# SCH_Breadboard_2022-07-15.net
KiCad netlist of a schematic drawn in EasyEDA
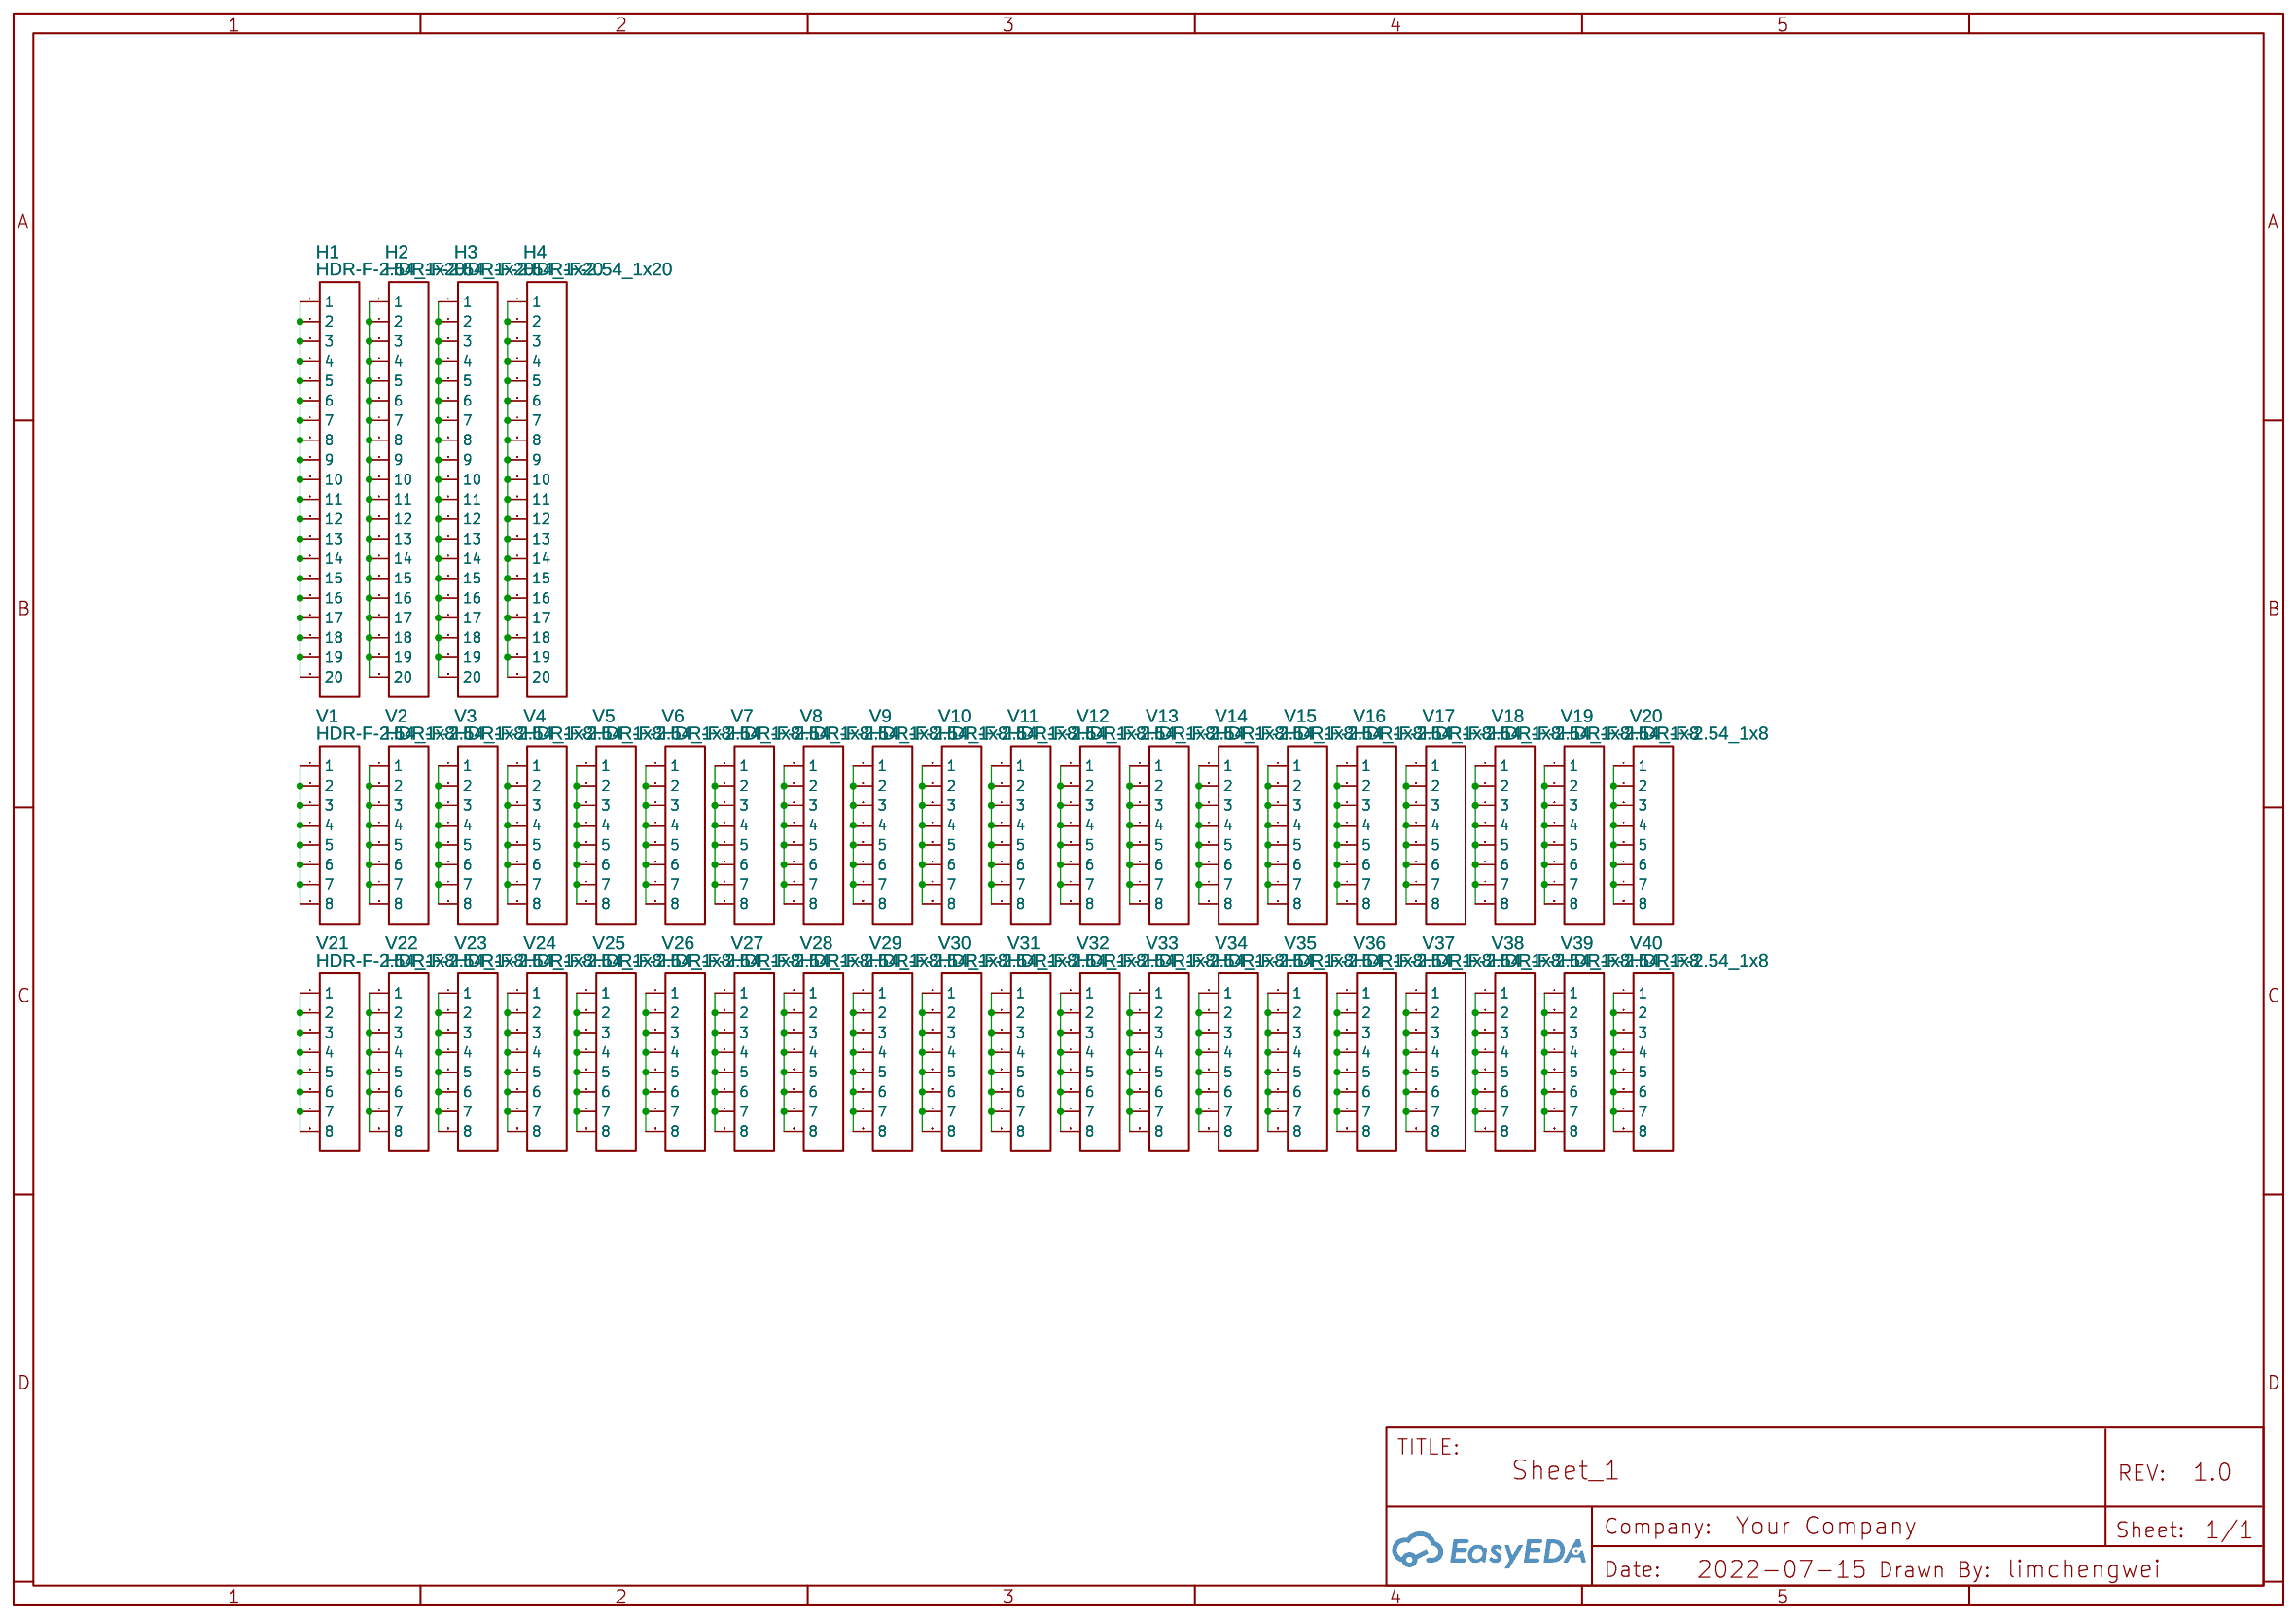
[diagram p0: schematic sheet]

(export (version "E")
  (design (tool "Eeschema 10.0.6"))
  (components
    (comp (ref "H1")
      (value "HDR-F-2.54_1x20")
      (fields (field (name "BOM_Supplier Part") "C50984"))
      (libsource (lib "") (part "HDR-F-2.54_1x20"))
    )
    (comp (ref "H2")
      (value "HDR-F-2.54_1x20")
      (fields (field (name "BOM_Supplier Part") "C50984"))
      (libsource (lib "") (part "HDR-F-2.54_1x20"))
    )
    (comp (ref "H3")
      (value "HDR-F-2.54_1x20")
      (fields (field (name "BOM_Supplier Part") "C50984"))
      (libsource (lib "") (part "HDR-F-2.54_1x20"))
    )
    (comp (ref "H4")
      (value "HDR-F-2.54_1x20")
      (fields (field (name "BOM_Supplier Part") "C50984"))
      (libsource (lib "") (part "HDR-F-2.54_1x20"))
    )
    (comp (ref "V1")
      (value "HDR-F-2.54_1x8")
      (fields (field (name "BOM_Supplier Part") "C225505"))
      (libsource (lib "") (part "HDR-F-2.54_1x8"))
    )
    (comp (ref "V2")
      (value "HDR-F-2.54_1x8")
      (fields (field (name "BOM_Supplier Part") "C225505"))
      (libsource (lib "") (part "HDR-F-2.54_1x8"))
    )
    (comp (ref "V3")
      (value "HDR-F-2.54_1x8")
      (fields (field (name "BOM_Supplier Part") "C225505"))
      (libsource (lib "") (part "HDR-F-2.54_1x8"))
    )
    (comp (ref "V4")
      (value "HDR-F-2.54_1x8")
      (fields (field (name "BOM_Supplier Part") "C225505"))
      (libsource (lib "") (part "HDR-F-2.54_1x8"))
    )
    (comp (ref "V5")
      (value "HDR-F-2.54_1x8")
      (fields (field (name "BOM_Supplier Part") "C225505"))
      (libsource (lib "") (part "HDR-F-2.54_1x8"))
    )
    (comp (ref "V6")
      (value "HDR-F-2.54_1x8")
      (fields (field (name "BOM_Supplier Part") "C225505"))
      (libsource (lib "") (part "HDR-F-2.54_1x8"))
    )
    (comp (ref "V7")
      (value "HDR-F-2.54_1x8")
      (fields (field (name "BOM_Supplier Part") "C225505"))
      (libsource (lib "") (part "HDR-F-2.54_1x8"))
    )
    (comp (ref "V8")
      (value "HDR-F-2.54_1x8")
      (fields (field (name "BOM_Supplier Part") "C225505"))
      (libsource (lib "") (part "HDR-F-2.54_1x8"))
    )
    (comp (ref "V9")
      (value "HDR-F-2.54_1x8")
      (fields (field (name "BOM_Supplier Part") "C225505"))
      (libsource (lib "") (part "HDR-F-2.54_1x8"))
    )
    (comp (ref "V10")
      (value "HDR-F-2.54_1x8")
      (fields (field (name "BOM_Supplier Part") "C225505"))
      (libsource (lib "") (part "HDR-F-2.54_1x8"))
    )
    (comp (ref "V11")
      (value "HDR-F-2.54_1x8")
      (fields (field (name "BOM_Supplier Part") "C225505"))
      (libsource (lib "") (part "HDR-F-2.54_1x8"))
    )
    (comp (ref "V12")
      (value "HDR-F-2.54_1x8")
      (fields (field (name "BOM_Supplier Part") "C225505"))
      (libsource (lib "") (part "HDR-F-2.54_1x8"))
    )
    (comp (ref "V13")
      (value "HDR-F-2.54_1x8")
      (fields (field (name "BOM_Supplier Part") "C225505"))
      (libsource (lib "") (part "HDR-F-2.54_1x8"))
    )
    (comp (ref "V14")
      (value "HDR-F-2.54_1x8")
      (fields (field (name "BOM_Supplier Part") "C225505"))
      (libsource (lib "") (part "HDR-F-2.54_1x8"))
    )
    (comp (ref "V15")
      (value "HDR-F-2.54_1x8")
      (fields (field (name "BOM_Supplier Part") "C225505"))
      (libsource (lib "") (part "HDR-F-2.54_1x8"))
    )
    (comp (ref "V16")
      (value "HDR-F-2.54_1x8")
      (fields (field (name "BOM_Supplier Part") "C225505"))
      (libsource (lib "") (part "HDR-F-2.54_1x8"))
    )
    (comp (ref "V17")
      (value "HDR-F-2.54_1x8")
      (fields (field (name "BOM_Supplier Part") "C225505"))
      (libsource (lib "") (part "HDR-F-2.54_1x8"))
    )
    (comp (ref "V18")
      (value "HDR-F-2.54_1x8")
      (fields (field (name "BOM_Supplier Part") "C225505"))
      (libsource (lib "") (part "HDR-F-2.54_1x8"))
    )
    (comp (ref "V19")
      (value "HDR-F-2.54_1x8")
      (fields (field (name "BOM_Supplier Part") "C225505"))
      (libsource (lib "") (part "HDR-F-2.54_1x8"))
    )
    (comp (ref "V20")
      (value "HDR-F-2.54_1x8")
      (fields (field (name "BOM_Supplier Part") "C225505"))
      (libsource (lib "") (part "HDR-F-2.54_1x8"))
    )
    (comp (ref "V21")
      (value "HDR-F-2.54_1x8")
      (fields (field (name "BOM_Supplier Part") "C225505"))
      (libsource (lib "") (part "HDR-F-2.54_1x8"))
    )
    (comp (ref "V22")
      (value "HDR-F-2.54_1x8")
      (fields (field (name "BOM_Supplier Part") "C225505"))
      (libsource (lib "") (part "HDR-F-2.54_1x8"))
    )
    (comp (ref "V23")
      (value "HDR-F-2.54_1x8")
      (fields (field (name "BOM_Supplier Part") "C225505"))
      (libsource (lib "") (part "HDR-F-2.54_1x8"))
    )
    (comp (ref "V24")
      (value "HDR-F-2.54_1x8")
      (fields (field (name "BOM_Supplier Part") "C225505"))
      (libsource (lib "") (part "HDR-F-2.54_1x8"))
    )
    (comp (ref "V25")
      (value "HDR-F-2.54_1x8")
      (fields (field (name "BOM_Supplier Part") "C225505"))
      (libsource (lib "") (part "HDR-F-2.54_1x8"))
    )
    (comp (ref "V26")
      (value "HDR-F-2.54_1x8")
      (fields (field (name "BOM_Supplier Part") "C225505"))
      (libsource (lib "") (part "HDR-F-2.54_1x8"))
    )
    (comp (ref "V27")
      (value "HDR-F-2.54_1x8")
      (fields (field (name "BOM_Supplier Part") "C225505"))
      (libsource (lib "") (part "HDR-F-2.54_1x8"))
    )
    (comp (ref "V28")
      (value "HDR-F-2.54_1x8")
      (fields (field (name "BOM_Supplier Part") "C225505"))
      (libsource (lib "") (part "HDR-F-2.54_1x8"))
    )
    (comp (ref "V29")
      (value "HDR-F-2.54_1x8")
      (fields (field (name "BOM_Supplier Part") "C225505"))
      (libsource (lib "") (part "HDR-F-2.54_1x8"))
    )
    (comp (ref "V30")
      (value "HDR-F-2.54_1x8")
      (fields (field (name "BOM_Supplier Part") "C225505"))
      (libsource (lib "") (part "HDR-F-2.54_1x8"))
    )
    (comp (ref "V31")
      (value "HDR-F-2.54_1x8")
      (fields (field (name "BOM_Supplier Part") "C225505"))
      (libsource (lib "") (part "HDR-F-2.54_1x8"))
    )
    (comp (ref "V32")
      (value "HDR-F-2.54_1x8")
      (fields (field (name "BOM_Supplier Part") "C225505"))
      (libsource (lib "") (part "HDR-F-2.54_1x8"))
    )
    (comp (ref "V33")
      (value "HDR-F-2.54_1x8")
      (fields (field (name "BOM_Supplier Part") "C225505"))
      (libsource (lib "") (part "HDR-F-2.54_1x8"))
    )
    (comp (ref "V34")
      (value "HDR-F-2.54_1x8")
      (fields (field (name "BOM_Supplier Part") "C225505"))
      (libsource (lib "") (part "HDR-F-2.54_1x8"))
    )
    (comp (ref "V35")
      (value "HDR-F-2.54_1x8")
      (fields (field (name "BOM_Supplier Part") "C225505"))
      (libsource (lib "") (part "HDR-F-2.54_1x8"))
    )
    (comp (ref "V36")
      (value "HDR-F-2.54_1x8")
      (fields (field (name "BOM_Supplier Part") "C225505"))
      (libsource (lib "") (part "HDR-F-2.54_1x8"))
    )
    (comp (ref "V37")
      (value "HDR-F-2.54_1x8")
      (fields (field (name "BOM_Supplier Part") "C225505"))
      (libsource (lib "") (part "HDR-F-2.54_1x8"))
    )
    (comp (ref "V38")
      (value "HDR-F-2.54_1x8")
      (fields (field (name "BOM_Supplier Part") "C225505"))
      (libsource (lib "") (part "HDR-F-2.54_1x8"))
    )
    (comp (ref "V39")
      (value "HDR-F-2.54_1x8")
      (fields (field (name "BOM_Supplier Part") "C225505"))
      (libsource (lib "") (part "HDR-F-2.54_1x8"))
    )
    (comp (ref "V40")
      (value "HDR-F-2.54_1x8")
      (fields (field (name "BOM_Supplier Part") "C225505"))
      (libsource (lib "") (part "HDR-F-2.54_1x8"))
    )
  )
  (nets
    (net (code "1") (name "Net-(H1-Pad1)") (class "Default")
      (node (ref "H1") (pin "1") (pinfunction "1_1") (pintype "unspecified"))
      (node (ref "H1") (pin "10") (pinfunction "10_10") (pintype "unspecified"))
      (node (ref "H1") (pin "11") (pinfunction "11_11") (pintype "unspecified"))
      (node (ref "H1") (pin "12") (pinfunction "12_12") (pintype "unspecified"))
      (node (ref "H1") (pin "13") (pinfunction "13_13") (pintype "unspecified"))
      (node (ref "H1") (pin "14") (pinfunction "14_14") (pintype "unspecified"))
      (node (ref "H1") (pin "15") (pinfunction "15_15") (pintype "unspecified"))
      (node (ref "H1") (pin "16") (pinfunction "16_16") (pintype "unspecified"))
      (node (ref "H1") (pin "17") (pinfunction "17_17") (pintype "unspecified"))
      (node (ref "H1") (pin "18") (pinfunction "18_18") (pintype "unspecified"))
      (node (ref "H1") (pin "19") (pinfunction "19_19") (pintype "unspecified"))
      (node (ref "H1") (pin "2") (pinfunction "2_2") (pintype "unspecified"))
      (node (ref "H1") (pin "20") (pinfunction "20_20") (pintype "unspecified"))
      (node (ref "H1") (pin "3") (pinfunction "3_3") (pintype "unspecified"))
      (node (ref "H1") (pin "4") (pinfunction "4_4") (pintype "unspecified"))
      (node (ref "H1") (pin "5") (pinfunction "5_5") (pintype "unspecified"))
      (node (ref "H1") (pin "6") (pinfunction "6_6") (pintype "unspecified"))
      (node (ref "H1") (pin "7") (pinfunction "7_7") (pintype "unspecified"))
      (node (ref "H1") (pin "8") (pinfunction "8_8") (pintype "unspecified"))
      (node (ref "H1") (pin "9") (pinfunction "9_9") (pintype "unspecified"))
    )
    (net (code "2") (name "Net-(H2-Pad1)") (class "Default")
      (node (ref "H2") (pin "1") (pinfunction "1_1") (pintype "unspecified"))
      (node (ref "H2") (pin "10") (pinfunction "10_10") (pintype "unspecified"))
      (node (ref "H2") (pin "11") (pinfunction "11_11") (pintype "unspecified"))
      (node (ref "H2") (pin "12") (pinfunction "12_12") (pintype "unspecified"))
      (node (ref "H2") (pin "13") (pinfunction "13_13") (pintype "unspecified"))
      (node (ref "H2") (pin "14") (pinfunction "14_14") (pintype "unspecified"))
      (node (ref "H2") (pin "15") (pinfunction "15_15") (pintype "unspecified"))
      (node (ref "H2") (pin "16") (pinfunction "16_16") (pintype "unspecified"))
      (node (ref "H2") (pin "17") (pinfunction "17_17") (pintype "unspecified"))
      (node (ref "H2") (pin "18") (pinfunction "18_18") (pintype "unspecified"))
      (node (ref "H2") (pin "19") (pinfunction "19_19") (pintype "unspecified"))
      (node (ref "H2") (pin "2") (pinfunction "2_2") (pintype "unspecified"))
      (node (ref "H2") (pin "20") (pinfunction "20_20") (pintype "unspecified"))
      (node (ref "H2") (pin "3") (pinfunction "3_3") (pintype "unspecified"))
      (node (ref "H2") (pin "4") (pinfunction "4_4") (pintype "unspecified"))
      (node (ref "H2") (pin "5") (pinfunction "5_5") (pintype "unspecified"))
      (node (ref "H2") (pin "6") (pinfunction "6_6") (pintype "unspecified"))
      (node (ref "H2") (pin "7") (pinfunction "7_7") (pintype "unspecified"))
      (node (ref "H2") (pin "8") (pinfunction "8_8") (pintype "unspecified"))
      (node (ref "H2") (pin "9") (pinfunction "9_9") (pintype "unspecified"))
    )
    (net (code "3") (name "Net-(H3-Pad1)") (class "Default")
      (node (ref "H3") (pin "1") (pinfunction "1_1") (pintype "unspecified"))
      (node (ref "H3") (pin "10") (pinfunction "10_10") (pintype "unspecified"))
      (node (ref "H3") (pin "11") (pinfunction "11_11") (pintype "unspecified"))
      (node (ref "H3") (pin "12") (pinfunction "12_12") (pintype "unspecified"))
      (node (ref "H3") (pin "13") (pinfunction "13_13") (pintype "unspecified"))
      (node (ref "H3") (pin "14") (pinfunction "14_14") (pintype "unspecified"))
      (node (ref "H3") (pin "15") (pinfunction "15_15") (pintype "unspecified"))
      (node (ref "H3") (pin "16") (pinfunction "16_16") (pintype "unspecified"))
      (node (ref "H3") (pin "17") (pinfunction "17_17") (pintype "unspecified"))
      (node (ref "H3") (pin "18") (pinfunction "18_18") (pintype "unspecified"))
      (node (ref "H3") (pin "19") (pinfunction "19_19") (pintype "unspecified"))
      (node (ref "H3") (pin "2") (pinfunction "2_2") (pintype "unspecified"))
      (node (ref "H3") (pin "20") (pinfunction "20_20") (pintype "unspecified"))
      (node (ref "H3") (pin "3") (pinfunction "3_3") (pintype "unspecified"))
      (node (ref "H3") (pin "4") (pinfunction "4_4") (pintype "unspecified"))
      (node (ref "H3") (pin "5") (pinfunction "5_5") (pintype "unspecified"))
      (node (ref "H3") (pin "6") (pinfunction "6_6") (pintype "unspecified"))
      (node (ref "H3") (pin "7") (pinfunction "7_7") (pintype "unspecified"))
      (node (ref "H3") (pin "8") (pinfunction "8_8") (pintype "unspecified"))
      (node (ref "H3") (pin "9") (pinfunction "9_9") (pintype "unspecified"))
    )
    (net (code "4") (name "Net-(H4-Pad1)") (class "Default")
      (node (ref "H4") (pin "1") (pinfunction "1_1") (pintype "unspecified"))
      (node (ref "H4") (pin "10") (pinfunction "10_10") (pintype "unspecified"))
      (node (ref "H4") (pin "11") (pinfunction "11_11") (pintype "unspecified"))
      (node (ref "H4") (pin "12") (pinfunction "12_12") (pintype "unspecified"))
      (node (ref "H4") (pin "13") (pinfunction "13_13") (pintype "unspecified"))
      (node (ref "H4") (pin "14") (pinfunction "14_14") (pintype "unspecified"))
      (node (ref "H4") (pin "15") (pinfunction "15_15") (pintype "unspecified"))
      (node (ref "H4") (pin "16") (pinfunction "16_16") (pintype "unspecified"))
      (node (ref "H4") (pin "17") (pinfunction "17_17") (pintype "unspecified"))
      (node (ref "H4") (pin "18") (pinfunction "18_18") (pintype "unspecified"))
      (node (ref "H4") (pin "19") (pinfunction "19_19") (pintype "unspecified"))
      (node (ref "H4") (pin "2") (pinfunction "2_2") (pintype "unspecified"))
      (node (ref "H4") (pin "20") (pinfunction "20_20") (pintype "unspecified"))
      (node (ref "H4") (pin "3") (pinfunction "3_3") (pintype "unspecified"))
      (node (ref "H4") (pin "4") (pinfunction "4_4") (pintype "unspecified"))
      (node (ref "H4") (pin "5") (pinfunction "5_5") (pintype "unspecified"))
      (node (ref "H4") (pin "6") (pinfunction "6_6") (pintype "unspecified"))
      (node (ref "H4") (pin "7") (pinfunction "7_7") (pintype "unspecified"))
      (node (ref "H4") (pin "8") (pinfunction "8_8") (pintype "unspecified"))
      (node (ref "H4") (pin "9") (pinfunction "9_9") (pintype "unspecified"))
    )
    (net (code "5") (name "Net-(V1-Pad1)") (class "Default")
      (node (ref "V1") (pin "1") (pinfunction "1_1") (pintype "unspecified"))
      (node (ref "V1") (pin "2") (pinfunction "2_2") (pintype "unspecified"))
      (node (ref "V1") (pin "3") (pinfunction "3_3") (pintype "unspecified"))
      (node (ref "V1") (pin "4") (pinfunction "4_4") (pintype "unspecified"))
      (node (ref "V1") (pin "5") (pinfunction "5_5") (pintype "unspecified"))
      (node (ref "V1") (pin "6") (pinfunction "6_6") (pintype "unspecified"))
      (node (ref "V1") (pin "7") (pinfunction "7_7") (pintype "unspecified"))
      (node (ref "V1") (pin "8") (pinfunction "8_8") (pintype "unspecified"))
    )
    (net (code "6") (name "Net-(V2-Pad1)") (class "Default")
      (node (ref "V2") (pin "1") (pinfunction "1_1") (pintype "unspecified"))
      (node (ref "V2") (pin "2") (pinfunction "2_2") (pintype "unspecified"))
      (node (ref "V2") (pin "3") (pinfunction "3_3") (pintype "unspecified"))
      (node (ref "V2") (pin "4") (pinfunction "4_4") (pintype "unspecified"))
      (node (ref "V2") (pin "5") (pinfunction "5_5") (pintype "unspecified"))
      (node (ref "V2") (pin "6") (pinfunction "6_6") (pintype "unspecified"))
      (node (ref "V2") (pin "7") (pinfunction "7_7") (pintype "unspecified"))
      (node (ref "V2") (pin "8") (pinfunction "8_8") (pintype "unspecified"))
    )
    (net (code "7") (name "Net-(V3-Pad1)") (class "Default")
      (node (ref "V3") (pin "1") (pinfunction "1_1") (pintype "unspecified"))
      (node (ref "V3") (pin "2") (pinfunction "2_2") (pintype "unspecified"))
      (node (ref "V3") (pin "3") (pinfunction "3_3") (pintype "unspecified"))
      (node (ref "V3") (pin "4") (pinfunction "4_4") (pintype "unspecified"))
      (node (ref "V3") (pin "5") (pinfunction "5_5") (pintype "unspecified"))
      (node (ref "V3") (pin "6") (pinfunction "6_6") (pintype "unspecified"))
      (node (ref "V3") (pin "7") (pinfunction "7_7") (pintype "unspecified"))
      (node (ref "V3") (pin "8") (pinfunction "8_8") (pintype "unspecified"))
    )
    (net (code "8") (name "Net-(V4-Pad1)") (class "Default")
      (node (ref "V4") (pin "1") (pinfunction "1_1") (pintype "unspecified"))
      (node (ref "V4") (pin "2") (pinfunction "2_2") (pintype "unspecified"))
      (node (ref "V4") (pin "3") (pinfunction "3_3") (pintype "unspecified"))
      (node (ref "V4") (pin "4") (pinfunction "4_4") (pintype "unspecified"))
      (node (ref "V4") (pin "5") (pinfunction "5_5") (pintype "unspecified"))
      (node (ref "V4") (pin "6") (pinfunction "6_6") (pintype "unspecified"))
      (node (ref "V4") (pin "7") (pinfunction "7_7") (pintype "unspecified"))
      (node (ref "V4") (pin "8") (pinfunction "8_8") (pintype "unspecified"))
    )
    (net (code "9") (name "Net-(V5-Pad1)") (class "Default")
      (node (ref "V5") (pin "1") (pinfunction "1_1") (pintype "unspecified"))
      (node (ref "V5") (pin "2") (pinfunction "2_2") (pintype "unspecified"))
      (node (ref "V5") (pin "3") (pinfunction "3_3") (pintype "unspecified"))
      (node (ref "V5") (pin "4") (pinfunction "4_4") (pintype "unspecified"))
      (node (ref "V5") (pin "5") (pinfunction "5_5") (pintype "unspecified"))
      (node (ref "V5") (pin "6") (pinfunction "6_6") (pintype "unspecified"))
      (node (ref "V5") (pin "7") (pinfunction "7_7") (pintype "unspecified"))
      (node (ref "V5") (pin "8") (pinfunction "8_8") (pintype "unspecified"))
    )
    (net (code "10") (name "Net-(V6-Pad1)") (class "Default")
      (node (ref "V6") (pin "1") (pinfunction "1_1") (pintype "unspecified"))
      (node (ref "V6") (pin "2") (pinfunction "2_2") (pintype "unspecified"))
      (node (ref "V6") (pin "3") (pinfunction "3_3") (pintype "unspecified"))
      (node (ref "V6") (pin "4") (pinfunction "4_4") (pintype "unspecified"))
      (node (ref "V6") (pin "5") (pinfunction "5_5") (pintype "unspecified"))
      (node (ref "V6") (pin "6") (pinfunction "6_6") (pintype "unspecified"))
      (node (ref "V6") (pin "7") (pinfunction "7_7") (pintype "unspecified"))
      (node (ref "V6") (pin "8") (pinfunction "8_8") (pintype "unspecified"))
    )
    (net (code "11") (name "Net-(V7-Pad1)") (class "Default")
      (node (ref "V7") (pin "1") (pinfunction "1_1") (pintype "unspecified"))
      (node (ref "V7") (pin "2") (pinfunction "2_2") (pintype "unspecified"))
      (node (ref "V7") (pin "3") (pinfunction "3_3") (pintype "unspecified"))
      (node (ref "V7") (pin "4") (pinfunction "4_4") (pintype "unspecified"))
      (node (ref "V7") (pin "5") (pinfunction "5_5") (pintype "unspecified"))
      (node (ref "V7") (pin "6") (pinfunction "6_6") (pintype "unspecified"))
      (node (ref "V7") (pin "7") (pinfunction "7_7") (pintype "unspecified"))
      (node (ref "V7") (pin "8") (pinfunction "8_8") (pintype "unspecified"))
    )
    (net (code "12") (name "Net-(V8-Pad1)") (class "Default")
      (node (ref "V8") (pin "1") (pinfunction "1_1") (pintype "unspecified"))
      (node (ref "V8") (pin "2") (pinfunction "2_2") (pintype "unspecified"))
      (node (ref "V8") (pin "3") (pinfunction "3_3") (pintype "unspecified"))
      (node (ref "V8") (pin "4") (pinfunction "4_4") (pintype "unspecified"))
      (node (ref "V8") (pin "5") (pinfunction "5_5") (pintype "unspecified"))
      (node (ref "V8") (pin "6") (pinfunction "6_6") (pintype "unspecified"))
      (node (ref "V8") (pin "7") (pinfunction "7_7") (pintype "unspecified"))
      (node (ref "V8") (pin "8") (pinfunction "8_8") (pintype "unspecified"))
    )
    (net (code "13") (name "Net-(V9-Pad1)") (class "Default")
      (node (ref "V9") (pin "1") (pinfunction "1_1") (pintype "unspecified"))
      (node (ref "V9") (pin "2") (pinfunction "2_2") (pintype "unspecified"))
      (node (ref "V9") (pin "3") (pinfunction "3_3") (pintype "unspecified"))
      (node (ref "V9") (pin "4") (pinfunction "4_4") (pintype "unspecified"))
      (node (ref "V9") (pin "5") (pinfunction "5_5") (pintype "unspecified"))
      (node (ref "V9") (pin "6") (pinfunction "6_6") (pintype "unspecified"))
      (node (ref "V9") (pin "7") (pinfunction "7_7") (pintype "unspecified"))
      (node (ref "V9") (pin "8") (pinfunction "8_8") (pintype "unspecified"))
    )
    (net (code "14") (name "Net-(V10-Pad1)") (class "Default")
      (node (ref "V10") (pin "1") (pinfunction "1_1") (pintype "unspecified"))
      (node (ref "V10") (pin "2") (pinfunction "2_2") (pintype "unspecified"))
      (node (ref "V10") (pin "3") (pinfunction "3_3") (pintype "unspecified"))
      (node (ref "V10") (pin "4") (pinfunction "4_4") (pintype "unspecified"))
      (node (ref "V10") (pin "5") (pinfunction "5_5") (pintype "unspecified"))
      (node (ref "V10") (pin "6") (pinfunction "6_6") (pintype "unspecified"))
      (node (ref "V10") (pin "7") (pinfunction "7_7") (pintype "unspecified"))
      (node (ref "V10") (pin "8") (pinfunction "8_8") (pintype "unspecified"))
    )
    (net (code "15") (name "Net-(V11-Pad1)") (class "Default")
      (node (ref "V11") (pin "1") (pinfunction "1_1") (pintype "unspecified"))
      (node (ref "V11") (pin "2") (pinfunction "2_2") (pintype "unspecified"))
      (node (ref "V11") (pin "3") (pinfunction "3_3") (pintype "unspecified"))
      (node (ref "V11") (pin "4") (pinfunction "4_4") (pintype "unspecified"))
      (node (ref "V11") (pin "5") (pinfunction "5_5") (pintype "unspecified"))
      (node (ref "V11") (pin "6") (pinfunction "6_6") (pintype "unspecified"))
      (node (ref "V11") (pin "7") (pinfunction "7_7") (pintype "unspecified"))
      (node (ref "V11") (pin "8") (pinfunction "8_8") (pintype "unspecified"))
    )
    (net (code "16") (name "Net-(V12-Pad1)") (class "Default")
      (node (ref "V12") (pin "1") (pinfunction "1_1") (pintype "unspecified"))
      (node (ref "V12") (pin "2") (pinfunction "2_2") (pintype "unspecified"))
      (node (ref "V12") (pin "3") (pinfunction "3_3") (pintype "unspecified"))
      (node (ref "V12") (pin "4") (pinfunction "4_4") (pintype "unspecified"))
      (node (ref "V12") (pin "5") (pinfunction "5_5") (pintype "unspecified"))
      (node (ref "V12") (pin "6") (pinfunction "6_6") (pintype "unspecified"))
      (node (ref "V12") (pin "7") (pinfunction "7_7") (pintype "unspecified"))
      (node (ref "V12") (pin "8") (pinfunction "8_8") (pintype "unspecified"))
    )
    (net (code "17") (name "Net-(V13-Pad1)") (class "Default")
      (node (ref "V13") (pin "1") (pinfunction "1_1") (pintype "unspecified"))
      (node (ref "V13") (pin "2") (pinfunction "2_2") (pintype "unspecified"))
      (node (ref "V13") (pin "3") (pinfunction "3_3") (pintype "unspecified"))
      (node (ref "V13") (pin "4") (pinfunction "4_4") (pintype "unspecified"))
      (node (ref "V13") (pin "5") (pinfunction "5_5") (pintype "unspecified"))
      (node (ref "V13") (pin "6") (pinfunction "6_6") (pintype "unspecified"))
      (node (ref "V13") (pin "7") (pinfunction "7_7") (pintype "unspecified"))
      (node (ref "V13") (pin "8") (pinfunction "8_8") (pintype "unspecified"))
    )
    (net (code "18") (name "Net-(V14-Pad1)") (class "Default")
      (node (ref "V14") (pin "1") (pinfunction "1_1") (pintype "unspecified"))
      (node (ref "V14") (pin "2") (pinfunction "2_2") (pintype "unspecified"))
      (node (ref "V14") (pin "3") (pinfunction "3_3") (pintype "unspecified"))
      (node (ref "V14") (pin "4") (pinfunction "4_4") (pintype "unspecified"))
      (node (ref "V14") (pin "5") (pinfunction "5_5") (pintype "unspecified"))
      (node (ref "V14") (pin "6") (pinfunction "6_6") (pintype "unspecified"))
      (node (ref "V14") (pin "7") (pinfunction "7_7") (pintype "unspecified"))
      (node (ref "V14") (pin "8") (pinfunction "8_8") (pintype "unspecified"))
    )
    (net (code "19") (name "Net-(V15-Pad1)") (class "Default")
      (node (ref "V15") (pin "1") (pinfunction "1_1") (pintype "unspecified"))
      (node (ref "V15") (pin "2") (pinfunction "2_2") (pintype "unspecified"))
      (node (ref "V15") (pin "3") (pinfunction "3_3") (pintype "unspecified"))
      (node (ref "V15") (pin "4") (pinfunction "4_4") (pintype "unspecified"))
      (node (ref "V15") (pin "5") (pinfunction "5_5") (pintype "unspecified"))
      (node (ref "V15") (pin "6") (pinfunction "6_6") (pintype "unspecified"))
      (node (ref "V15") (pin "7") (pinfunction "7_7") (pintype "unspecified"))
      (node (ref "V15") (pin "8") (pinfunction "8_8") (pintype "unspecified"))
    )
    (net (code "20") (name "Net-(V16-Pad1)") (class "Default")
      (node (ref "V16") (pin "1") (pinfunction "1_1") (pintype "unspecified"))
      (node (ref "V16") (pin "2") (pinfunction "2_2") (pintype "unspecified"))
      (node (ref "V16") (pin "3") (pinfunction "3_3") (pintype "unspecified"))
      (node (ref "V16") (pin "4") (pinfunction "4_4") (pintype "unspecified"))
      (node (ref "V16") (pin "5") (pinfunction "5_5") (pintype "unspecified"))
      (node (ref "V16") (pin "6") (pinfunction "6_6") (pintype "unspecified"))
      (node (ref "V16") (pin "7") (pinfunction "7_7") (pintype "unspecified"))
      (node (ref "V16") (pin "8") (pinfunction "8_8") (pintype "unspecified"))
    )
    (net (code "21") (name "Net-(V17-Pad1)") (class "Default")
      (node (ref "V17") (pin "1") (pinfunction "1_1") (pintype "unspecified"))
      (node (ref "V17") (pin "2") (pinfunction "2_2") (pintype "unspecified"))
      (node (ref "V17") (pin "3") (pinfunction "3_3") (pintype "unspecified"))
      (node (ref "V17") (pin "4") (pinfunction "4_4") (pintype "unspecified"))
      (node (ref "V17") (pin "5") (pinfunction "5_5") (pintype "unspecified"))
      (node (ref "V17") (pin "6") (pinfunction "6_6") (pintype "unspecified"))
      (node (ref "V17") (pin "7") (pinfunction "7_7") (pintype "unspecified"))
      (node (ref "V17") (pin "8") (pinfunction "8_8") (pintype "unspecified"))
    )
    (net (code "22") (name "Net-(V18-Pad1)") (class "Default")
      (node (ref "V18") (pin "1") (pinfunction "1_1") (pintype "unspecified"))
      (node (ref "V18") (pin "2") (pinfunction "2_2") (pintype "unspecified"))
      (node (ref "V18") (pin "3") (pinfunction "3_3") (pintype "unspecified"))
      (node (ref "V18") (pin "4") (pinfunction "4_4") (pintype "unspecified"))
      (node (ref "V18") (pin "5") (pinfunction "5_5") (pintype "unspecified"))
      (node (ref "V18") (pin "6") (pinfunction "6_6") (pintype "unspecified"))
      (node (ref "V18") (pin "7") (pinfunction "7_7") (pintype "unspecified"))
      (node (ref "V18") (pin "8") (pinfunction "8_8") (pintype "unspecified"))
    )
    (net (code "23") (name "Net-(V19-Pad1)") (class "Default")
      (node (ref "V19") (pin "1") (pinfunction "1_1") (pintype "unspecified"))
      (node (ref "V19") (pin "2") (pinfunction "2_2") (pintype "unspecified"))
      (node (ref "V19") (pin "3") (pinfunction "3_3") (pintype "unspecified"))
      (node (ref "V19") (pin "4") (pinfunction "4_4") (pintype "unspecified"))
      (node (ref "V19") (pin "5") (pinfunction "5_5") (pintype "unspecified"))
      (node (ref "V19") (pin "6") (pinfunction "6_6") (pintype "unspecified"))
      (node (ref "V19") (pin "7") (pinfunction "7_7") (pintype "unspecified"))
      (node (ref "V19") (pin "8") (pinfunction "8_8") (pintype "unspecified"))
    )
    (net (code "24") (name "Net-(V20-Pad1)") (class "Default")
      (node (ref "V20") (pin "1") (pinfunction "1_1") (pintype "unspecified"))
      (node (ref "V20") (pin "2") (pinfunction "2_2") (pintype "unspecified"))
      (node (ref "V20") (pin "3") (pinfunction "3_3") (pintype "unspecified"))
      (node (ref "V20") (pin "4") (pinfunction "4_4") (pintype "unspecified"))
      (node (ref "V20") (pin "5") (pinfunction "5_5") (pintype "unspecified"))
      (node (ref "V20") (pin "6") (pinfunction "6_6") (pintype "unspecified"))
      (node (ref "V20") (pin "7") (pinfunction "7_7") (pintype "unspecified"))
      (node (ref "V20") (pin "8") (pinfunction "8_8") (pintype "unspecified"))
    )
    (net (code "25") (name "Net-(V21-Pad1)") (class "Default")
      (node (ref "V21") (pin "1") (pinfunction "1_1") (pintype "unspecified"))
      (node (ref "V21") (pin "2") (pinfunction "2_2") (pintype "unspecified"))
      (node (ref "V21") (pin "3") (pinfunction "3_3") (pintype "unspecified"))
      (node (ref "V21") (pin "4") (pinfunction "4_4") (pintype "unspecified"))
      (node (ref "V21") (pin "5") (pinfunction "5_5") (pintype "unspecified"))
      (node (ref "V21") (pin "6") (pinfunction "6_6") (pintype "unspecified"))
      (node (ref "V21") (pin "7") (pinfunction "7_7") (pintype "unspecified"))
      (node (ref "V21") (pin "8") (pinfunction "8_8") (pintype "unspecified"))
    )
    (net (code "26") (name "Net-(V22-Pad1)") (class "Default")
      (node (ref "V22") (pin "1") (pinfunction "1_1") (pintype "unspecified"))
      (node (ref "V22") (pin "2") (pinfunction "2_2") (pintype "unspecified"))
      (node (ref "V22") (pin "3") (pinfunction "3_3") (pintype "unspecified"))
      (node (ref "V22") (pin "4") (pinfunction "4_4") (pintype "unspecified"))
      (node (ref "V22") (pin "5") (pinfunction "5_5") (pintype "unspecified"))
      (node (ref "V22") (pin "6") (pinfunction "6_6") (pintype "unspecified"))
      (node (ref "V22") (pin "7") (pinfunction "7_7") (pintype "unspecified"))
      (node (ref "V22") (pin "8") (pinfunction "8_8") (pintype "unspecified"))
    )
    (net (code "27") (name "Net-(V23-Pad1)") (class "Default")
      (node (ref "V23") (pin "1") (pinfunction "1_1") (pintype "unspecified"))
      (node (ref "V23") (pin "2") (pinfunction "2_2") (pintype "unspecified"))
      (node (ref "V23") (pin "3") (pinfunction "3_3") (pintype "unspecified"))
      (node (ref "V23") (pin "4") (pinfunction "4_4") (pintype "unspecified"))
      (node (ref "V23") (pin "5") (pinfunction "5_5") (pintype "unspecified"))
      (node (ref "V23") (pin "6") (pinfunction "6_6") (pintype "unspecified"))
      (node (ref "V23") (pin "7") (pinfunction "7_7") (pintype "unspecified"))
      (node (ref "V23") (pin "8") (pinfunction "8_8") (pintype "unspecified"))
    )
    (net (code "28") (name "Net-(V24-Pad1)") (class "Default")
      (node (ref "V24") (pin "1") (pinfunction "1_1") (pintype "unspecified"))
      (node (ref "V24") (pin "2") (pinfunction "2_2") (pintype "unspecified"))
      (node (ref "V24") (pin "3") (pinfunction "3_3") (pintype "unspecified"))
      (node (ref "V24") (pin "4") (pinfunction "4_4") (pintype "unspecified"))
      (node (ref "V24") (pin "5") (pinfunction "5_5") (pintype "unspecified"))
      (node (ref "V24") (pin "6") (pinfunction "6_6") (pintype "unspecified"))
      (node (ref "V24") (pin "7") (pinfunction "7_7") (pintype "unspecified"))
      (node (ref "V24") (pin "8") (pinfunction "8_8") (pintype "unspecified"))
    )
    (net (code "29") (name "Net-(V25-Pad1)") (class "Default")
      (node (ref "V25") (pin "1") (pinfunction "1_1") (pintype "unspecified"))
      (node (ref "V25") (pin "2") (pinfunction "2_2") (pintype "unspecified"))
      (node (ref "V25") (pin "3") (pinfunction "3_3") (pintype "unspecified"))
      (node (ref "V25") (pin "4") (pinfunction "4_4") (pintype "unspecified"))
      (node (ref "V25") (pin "5") (pinfunction "5_5") (pintype "unspecified"))
      (node (ref "V25") (pin "6") (pinfunction "6_6") (pintype "unspecified"))
      (node (ref "V25") (pin "7") (pinfunction "7_7") (pintype "unspecified"))
      (node (ref "V25") (pin "8") (pinfunction "8_8") (pintype "unspecified"))
    )
    (net (code "30") (name "Net-(V26-Pad1)") (class "Default")
      (node (ref "V26") (pin "1") (pinfunction "1_1") (pintype "unspecified"))
      (node (ref "V26") (pin "2") (pinfunction "2_2") (pintype "unspecified"))
      (node (ref "V26") (pin "3") (pinfunction "3_3") (pintype "unspecified"))
      (node (ref "V26") (pin "4") (pinfunction "4_4") (pintype "unspecified"))
      (node (ref "V26") (pin "5") (pinfunction "5_5") (pintype "unspecified"))
      (node (ref "V26") (pin "6") (pinfunction "6_6") (pintype "unspecified"))
      (node (ref "V26") (pin "7") (pinfunction "7_7") (pintype "unspecified"))
      (node (ref "V26") (pin "8") (pinfunction "8_8") (pintype "unspecified"))
    )
    (net (code "31") (name "Net-(V27-Pad1)") (class "Default")
      (node (ref "V27") (pin "1") (pinfunction "1_1") (pintype "unspecified"))
      (node (ref "V27") (pin "2") (pinfunction "2_2") (pintype "unspecified"))
      (node (ref "V27") (pin "3") (pinfunction "3_3") (pintype "unspecified"))
      (node (ref "V27") (pin "4") (pinfunction "4_4") (pintype "unspecified"))
      (node (ref "V27") (pin "5") (pinfunction "5_5") (pintype "unspecified"))
      (node (ref "V27") (pin "6") (pinfunction "6_6") (pintype "unspecified"))
      (node (ref "V27") (pin "7") (pinfunction "7_7") (pintype "unspecified"))
      (node (ref "V27") (pin "8") (pinfunction "8_8") (pintype "unspecified"))
    )
    (net (code "32") (name "Net-(V28-Pad1)") (class "Default")
      (node (ref "V28") (pin "1") (pinfunction "1_1") (pintype "unspecified"))
      (node (ref "V28") (pin "2") (pinfunction "2_2") (pintype "unspecified"))
      (node (ref "V28") (pin "3") (pinfunction "3_3") (pintype "unspecified"))
      (node (ref "V28") (pin "4") (pinfunction "4_4") (pintype "unspecified"))
      (node (ref "V28") (pin "5") (pinfunction "5_5") (pintype "unspecified"))
      (node (ref "V28") (pin "6") (pinfunction "6_6") (pintype "unspecified"))
      (node (ref "V28") (pin "7") (pinfunction "7_7") (pintype "unspecified"))
      (node (ref "V28") (pin "8") (pinfunction "8_8") (pintype "unspecified"))
    )
    (net (code "33") (name "Net-(V29-Pad1)") (class "Default")
      (node (ref "V29") (pin "1") (pinfunction "1_1") (pintype "unspecified"))
      (node (ref "V29") (pin "2") (pinfunction "2_2") (pintype "unspecified"))
      (node (ref "V29") (pin "3") (pinfunction "3_3") (pintype "unspecified"))
      (node (ref "V29") (pin "4") (pinfunction "4_4") (pintype "unspecified"))
      (node (ref "V29") (pin "5") (pinfunction "5_5") (pintype "unspecified"))
      (node (ref "V29") (pin "6") (pinfunction "6_6") (pintype "unspecified"))
      (node (ref "V29") (pin "7") (pinfunction "7_7") (pintype "unspecified"))
      (node (ref "V29") (pin "8") (pinfunction "8_8") (pintype "unspecified"))
    )
    (net (code "34") (name "Net-(V30-Pad1)") (class "Default")
      (node (ref "V30") (pin "1") (pinfunction "1_1") (pintype "unspecified"))
      (node (ref "V30") (pin "2") (pinfunction "2_2") (pintype "unspecified"))
      (node (ref "V30") (pin "3") (pinfunction "3_3") (pintype "unspecified"))
      (node (ref "V30") (pin "4") (pinfunction "4_4") (pintype "unspecified"))
      (node (ref "V30") (pin "5") (pinfunction "5_5") (pintype "unspecified"))
      (node (ref "V30") (pin "6") (pinfunction "6_6") (pintype "unspecified"))
      (node (ref "V30") (pin "7") (pinfunction "7_7") (pintype "unspecified"))
      (node (ref "V30") (pin "8") (pinfunction "8_8") (pintype "unspecified"))
    )
    (net (code "35") (name "Net-(V31-Pad1)") (class "Default")
      (node (ref "V31") (pin "1") (pinfunction "1_1") (pintype "unspecified"))
      (node (ref "V31") (pin "2") (pinfunction "2_2") (pintype "unspecified"))
      (node (ref "V31") (pin "3") (pinfunction "3_3") (pintype "unspecified"))
      (node (ref "V31") (pin "4") (pinfunction "4_4") (pintype "unspecified"))
      (node (ref "V31") (pin "5") (pinfunction "5_5") (pintype "unspecified"))
      (node (ref "V31") (pin "6") (pinfunction "6_6") (pintype "unspecified"))
      (node (ref "V31") (pin "7") (pinfunction "7_7") (pintype "unspecified"))
      (node (ref "V31") (pin "8") (pinfunction "8_8") (pintype "unspecified"))
    )
    (net (code "36") (name "Net-(V32-Pad1)") (class "Default")
      (node (ref "V32") (pin "1") (pinfunction "1_1") (pintype "unspecified"))
      (node (ref "V32") (pin "2") (pinfunction "2_2") (pintype "unspecified"))
      (node (ref "V32") (pin "3") (pinfunction "3_3") (pintype "unspecified"))
      (node (ref "V32") (pin "4") (pinfunction "4_4") (pintype "unspecified"))
      (node (ref "V32") (pin "5") (pinfunction "5_5") (pintype "unspecified"))
      (node (ref "V32") (pin "6") (pinfunction "6_6") (pintype "unspecified"))
      (node (ref "V32") (pin "7") (pinfunction "7_7") (pintype "unspecified"))
      (node (ref "V32") (pin "8") (pinfunction "8_8") (pintype "unspecified"))
    )
    (net (code "37") (name "Net-(V33-Pad1)") (class "Default")
      (node (ref "V33") (pin "1") (pinfunction "1_1") (pintype "unspecified"))
      (node (ref "V33") (pin "2") (pinfunction "2_2") (pintype "unspecified"))
      (node (ref "V33") (pin "3") (pinfunction "3_3") (pintype "unspecified"))
      (node (ref "V33") (pin "4") (pinfunction "4_4") (pintype "unspecified"))
      (node (ref "V33") (pin "5") (pinfunction "5_5") (pintype "unspecified"))
      (node (ref "V33") (pin "6") (pinfunction "6_6") (pintype "unspecified"))
      (node (ref "V33") (pin "7") (pinfunction "7_7") (pintype "unspecified"))
      (node (ref "V33") (pin "8") (pinfunction "8_8") (pintype "unspecified"))
    )
    (net (code "38") (name "Net-(V34-Pad1)") (class "Default")
      (node (ref "V34") (pin "1") (pinfunction "1_1") (pintype "unspecified"))
      (node (ref "V34") (pin "2") (pinfunction "2_2") (pintype "unspecified"))
      (node (ref "V34") (pin "3") (pinfunction "3_3") (pintype "unspecified"))
      (node (ref "V34") (pin "4") (pinfunction "4_4") (pintype "unspecified"))
      (node (ref "V34") (pin "5") (pinfunction "5_5") (pintype "unspecified"))
      (node (ref "V34") (pin "6") (pinfunction "6_6") (pintype "unspecified"))
      (node (ref "V34") (pin "7") (pinfunction "7_7") (pintype "unspecified"))
      (node (ref "V34") (pin "8") (pinfunction "8_8") (pintype "unspecified"))
    )
    (net (code "39") (name "Net-(V35-Pad1)") (class "Default")
      (node (ref "V35") (pin "1") (pinfunction "1_1") (pintype "unspecified"))
      (node (ref "V35") (pin "2") (pinfunction "2_2") (pintype "unspecified"))
      (node (ref "V35") (pin "3") (pinfunction "3_3") (pintype "unspecified"))
      (node (ref "V35") (pin "4") (pinfunction "4_4") (pintype "unspecified"))
      (node (ref "V35") (pin "5") (pinfunction "5_5") (pintype "unspecified"))
      (node (ref "V35") (pin "6") (pinfunction "6_6") (pintype "unspecified"))
      (node (ref "V35") (pin "7") (pinfunction "7_7") (pintype "unspecified"))
      (node (ref "V35") (pin "8") (pinfunction "8_8") (pintype "unspecified"))
    )
    (net (code "40") (name "Net-(V36-Pad1)") (class "Default")
      (node (ref "V36") (pin "1") (pinfunction "1_1") (pintype "unspecified"))
      (node (ref "V36") (pin "2") (pinfunction "2_2") (pintype "unspecified"))
      (node (ref "V36") (pin "3") (pinfunction "3_3") (pintype "unspecified"))
      (node (ref "V36") (pin "4") (pinfunction "4_4") (pintype "unspecified"))
      (node (ref "V36") (pin "5") (pinfunction "5_5") (pintype "unspecified"))
      (node (ref "V36") (pin "6") (pinfunction "6_6") (pintype "unspecified"))
      (node (ref "V36") (pin "7") (pinfunction "7_7") (pintype "unspecified"))
      (node (ref "V36") (pin "8") (pinfunction "8_8") (pintype "unspecified"))
    )
    (net (code "41") (name "Net-(V37-Pad1)") (class "Default")
      (node (ref "V37") (pin "1") (pinfunction "1_1") (pintype "unspecified"))
      (node (ref "V37") (pin "2") (pinfunction "2_2") (pintype "unspecified"))
      (node (ref "V37") (pin "3") (pinfunction "3_3") (pintype "unspecified"))
      (node (ref "V37") (pin "4") (pinfunction "4_4") (pintype "unspecified"))
      (node (ref "V37") (pin "5") (pinfunction "5_5") (pintype "unspecified"))
      (node (ref "V37") (pin "6") (pinfunction "6_6") (pintype "unspecified"))
      (node (ref "V37") (pin "7") (pinfunction "7_7") (pintype "unspecified"))
      (node (ref "V37") (pin "8") (pinfunction "8_8") (pintype "unspecified"))
    )
    (net (code "42") (name "Net-(V38-Pad1)") (class "Default")
      (node (ref "V38") (pin "1") (pinfunction "1_1") (pintype "unspecified"))
      (node (ref "V38") (pin "2") (pinfunction "2_2") (pintype "unspecified"))
      (node (ref "V38") (pin "3") (pinfunction "3_3") (pintype "unspecified"))
      (node (ref "V38") (pin "4") (pinfunction "4_4") (pintype "unspecified"))
      (node (ref "V38") (pin "5") (pinfunction "5_5") (pintype "unspecified"))
      (node (ref "V38") (pin "6") (pinfunction "6_6") (pintype "unspecified"))
      (node (ref "V38") (pin "7") (pinfunction "7_7") (pintype "unspecified"))
      (node (ref "V38") (pin "8") (pinfunction "8_8") (pintype "unspecified"))
    )
    (net (code "43") (name "Net-(V39-Pad1)") (class "Default")
      (node (ref "V39") (pin "1") (pinfunction "1_1") (pintype "unspecified"))
      (node (ref "V39") (pin "2") (pinfunction "2_2") (pintype "unspecified"))
      (node (ref "V39") (pin "3") (pinfunction "3_3") (pintype "unspecified"))
      (node (ref "V39") (pin "4") (pinfunction "4_4") (pintype "unspecified"))
      (node (ref "V39") (pin "5") (pinfunction "5_5") (pintype "unspecified"))
      (node (ref "V39") (pin "6") (pinfunction "6_6") (pintype "unspecified"))
      (node (ref "V39") (pin "7") (pinfunction "7_7") (pintype "unspecified"))
      (node (ref "V39") (pin "8") (pinfunction "8_8") (pintype "unspecified"))
    )
    (net (code "44") (name "Net-(V40-Pad1)") (class "Default")
      (node (ref "V40") (pin "1") (pinfunction "1_1") (pintype "unspecified"))
      (node (ref "V40") (pin "2") (pinfunction "2_2") (pintype "unspecified"))
      (node (ref "V40") (pin "3") (pinfunction "3_3") (pintype "unspecified"))
      (node (ref "V40") (pin "4") (pinfunction "4_4") (pintype "unspecified"))
      (node (ref "V40") (pin "5") (pinfunction "5_5") (pintype "unspecified"))
      (node (ref "V40") (pin "6") (pinfunction "6_6") (pintype "unspecified"))
      (node (ref "V40") (pin "7") (pinfunction "7_7") (pintype "unspecified"))
      (node (ref "V40") (pin "8") (pinfunction "8_8") (pintype "unspecified"))
    )
  )
)
